# M501X.net
KiCad netlist of a schematic drawn in EAGLE
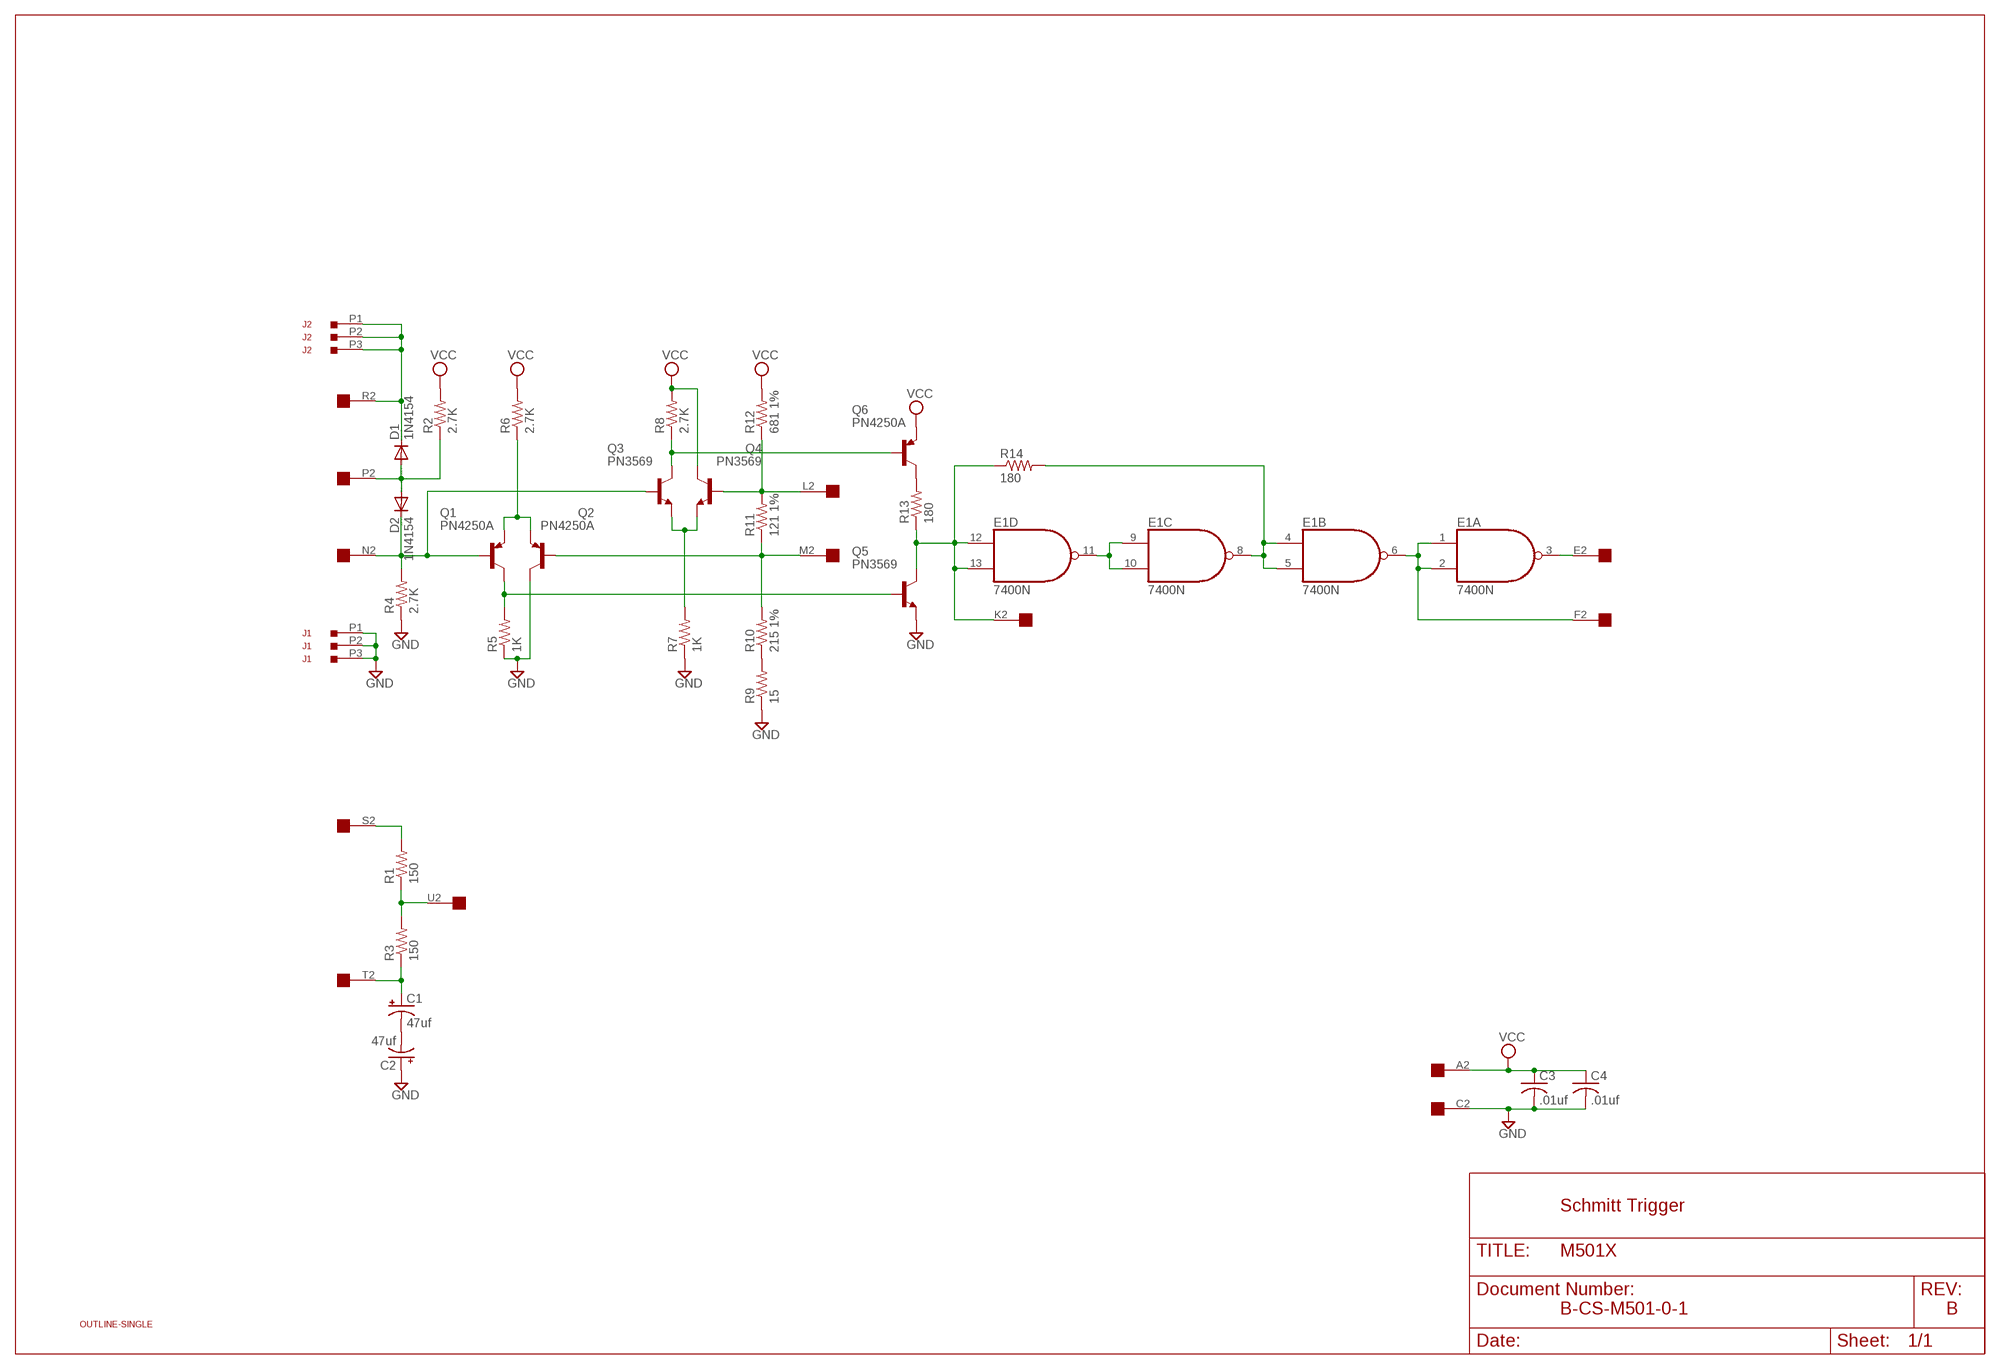
[diagram p0: schematic, sheet 1]

(export (version "E")
  (design (tool "Eeschema 10.0.6"))
  (components
    (comp (ref "C1")
      (value "47uf")
      (footprint "eagle-import:E22-6")
      (libsource (lib "eagle-import") (part "CPOL-USE22-6AXIAL"))
    )
    (comp (ref "C2")
      (value "47uf")
      (footprint "eagle-import:E22-6")
      (libsource (lib "eagle-import") (part "CPOL-USE22-6AXIAL"))
    )
    (comp (ref "C3")
      (value ".01uf")
      (footprint "eagle-import:C075-032X103")
      (libsource (lib "eagle-import") (part "C-US075-032X103"))
    )
    (comp (ref "C4")
      (value ".01uf")
      (footprint "eagle-import:C075-032X103")
      (libsource (lib "eagle-import") (part "C-US075-032X103"))
    )
    (comp (ref "D1")
      (value "1N4154")
      (footprint "eagle-import:DO35-10")
      (libsource (lib "eagle-import") (part "1N4148DO35-10"))
    )
    (comp (ref "D2")
      (value "1N4154")
      (footprint "eagle-import:DO35-10")
      (libsource (lib "eagle-import") (part "1N4148DO35-10"))
    )
    (comp (ref "E1")
      (value "7400N")
      (footprint "eagle-import:DIL14")
      (libsource (lib "eagle-import") (part "7400N"))
    )
    (comp (ref "J1")
      (value "34-22-1-03")
      (footprint "eagle-import:34-22-1-03")
      (libsource (lib "eagle-import") (part "34-22-1-03"))
    )
    (comp (ref "J2")
      (value "34-22-1-03")
      (footprint "eagle-import:34-22-1-03")
      (libsource (lib "eagle-import") (part "34-22-1-03"))
    )
    (comp (ref "Q1")
      (value "PN4250A")
      (footprint "eagle-import:TO39")
      (libsource (lib "eagle-import") (part "2N2904"))
    )
    (comp (ref "Q2")
      (value "PN4250A")
      (footprint "eagle-import:TO39")
      (libsource (lib "eagle-import") (part "2N2904"))
    )
    (comp (ref "Q3")
      (value "PN3569")
      (footprint "eagle-import:TO39")
      (libsource (lib "eagle-import") (part "2N3019"))
    )
    (comp (ref "Q4")
      (value "PN3569")
      (footprint "eagle-import:TO39")
      (libsource (lib "eagle-import") (part "2N3019"))
    )
    (comp (ref "Q5")
      (value "PN3569")
      (footprint "eagle-import:TO39")
      (libsource (lib "eagle-import") (part "2N3019"))
    )
    (comp (ref "Q6")
      (value "PN4250A")
      (footprint "eagle-import:TO39")
      (libsource (lib "eagle-import") (part "2N2904"))
    )
    (comp (ref "R1")
      (value "150")
      (footprint "eagle-import:0207_10")
      (libsource (lib "eagle-import") (part "R-US_0207/10"))
    )
    (comp (ref "R2")
      (value "2.7K")
      (footprint "eagle-import:0207_10")
      (libsource (lib "eagle-import") (part "R-US_0207/10"))
    )
    (comp (ref "R3")
      (value "150")
      (footprint "eagle-import:0207_10")
      (libsource (lib "eagle-import") (part "R-US_0207/10"))
    )
    (comp (ref "R4")
      (value "2.7K")
      (footprint "eagle-import:0207_10")
      (libsource (lib "eagle-import") (part "R-US_0207/10"))
    )
    (comp (ref "R5")
      (value "1K")
      (footprint "eagle-import:0207_10")
      (libsource (lib "eagle-import") (part "R-US_0207/10"))
    )
    (comp (ref "R6")
      (value "2.7K")
      (footprint "eagle-import:0207_10")
      (libsource (lib "eagle-import") (part "R-US_0207/10"))
    )
    (comp (ref "R7")
      (value "1K")
      (footprint "eagle-import:0207_10")
      (libsource (lib "eagle-import") (part "R-US_0207/10"))
    )
    (comp (ref "R8")
      (value "2.7K")
      (footprint "eagle-import:0207_10")
      (libsource (lib "eagle-import") (part "R-US_0207/10"))
    )
    (comp (ref "R9")
      (value "15")
      (footprint "eagle-import:0207_10")
      (libsource (lib "eagle-import") (part "R-US_0207/10"))
    )
    (comp (ref "R10")
      (value "215 1%")
      (footprint "eagle-import:0207_15")
      (libsource (lib "eagle-import") (part "R-US_0207/15"))
    )
    (comp (ref "R11")
      (value "121 1%")
      (footprint "eagle-import:0207_15")
      (libsource (lib "eagle-import") (part "R-US_0207/15"))
    )
    (comp (ref "R12")
      (value "681 1%")
      (footprint "eagle-import:0207_15")
      (libsource (lib "eagle-import") (part "R-US_0207/15"))
    )
    (comp (ref "R13")
      (value "180")
      (footprint "eagle-import:0207_10")
      (libsource (lib "eagle-import") (part "R-US_0207/10"))
    )
    (comp (ref "R14")
      (value "180")
      (footprint "eagle-import:0207_10")
      (libsource (lib "eagle-import") (part "R-US_0207/10"))
    )
    (comp (ref "U$1")
      (value "EDGE-1")
      (footprint "eagle-import:EDGE-CON1")
      (libsource (lib "eagle-import") (part "EDGE-1"))
    )
    (comp (ref "U$4")
      (value "OUTLINE-SINGLE")
      (footprint "eagle-import:SINGLE")
      (libsource (lib "eagle-import") (part "OUTLINE-SINGLE"))
    )
  )
  (nets
    (net (code "1") (name "GND") (class "Default")
      (node (ref "C2") (pin "+") (pinfunction "+_+") (pintype "passive"))
      (node (ref "C3") (pin "2") (pinfunction "2_2") (pintype "passive"))
      (node (ref "C4") (pin "2") (pinfunction "2_2") (pintype "passive"))
      (node (ref "J1") (pin "P1") (pinfunction "P$2_P1") (pintype "bidirectional"))
      (node (ref "J1") (pin "P2") (pinfunction "P$2_P2") (pintype "bidirectional"))
      (node (ref "J1") (pin "P3") (pinfunction "P$2_P3") (pintype "bidirectional"))
      (node (ref "Q2") (pin "3") (pinfunction "C_3") (pintype "passive"))
      (node (ref "Q5") (pin "1") (pinfunction "E_1") (pintype "passive"))
      (node (ref "R4") (pin "1") (pinfunction "1_1") (pintype "passive"))
      (node (ref "R5") (pin "1") (pinfunction "1_1") (pintype "passive"))
      (node (ref "R7") (pin "1") (pinfunction "1_1") (pintype "passive"))
      (node (ref "R9") (pin "1") (pinfunction "1_1") (pintype "passive"))
      (node (ref "U$1") (pin "C2") (pinfunction "1_C2") (pintype "bidirectional"))
    )
    (net (code "2") (name "Net-(C1-Pad-)") (class "Default")
      (node (ref "C1") (pin "-") (pinfunction "-_-") (pintype "passive"))
      (node (ref "C2") (pin "-") (pinfunction "-_-") (pintype "passive"))
    )
    (net (code "3") (name "Net-(E1A-I0)") (class "Default")
      (node (ref "E1") (pin "1") (pinfunction "I0_1") (pintype "input"))
      (node (ref "E1") (pin "2") (pinfunction "I1_2") (pintype "input"))
      (node (ref "E1") (pin "6") (pinfunction "O_6") (pintype "output"))
      (node (ref "U$1") (pin "F2") (pinfunction "1_F2") (pintype "bidirectional"))
    )
    (net (code "4") (name "Net-(E1A-O)") (class "Default")
      (node (ref "E1") (pin "3") (pinfunction "O_3") (pintype "output"))
      (node (ref "U$1") (pin "E2") (pinfunction "1_E2") (pintype "bidirectional"))
    )
    (net (code "5") (name "Net-(E1B-I0)") (class "Default")
      (node (ref "E1") (pin "4") (pinfunction "I0_4") (pintype "input"))
      (node (ref "E1") (pin "5") (pinfunction "I1_5") (pintype "input"))
      (node (ref "E1") (pin "8") (pinfunction "O_8") (pintype "output"))
      (node (ref "R14") (pin "2") (pinfunction "2_2") (pintype "passive"))
    )
    (net (code "6") (name "Net-(E1C-I0)") (class "Default")
      (node (ref "E1") (pin "10") (pinfunction "I1_10") (pintype "input"))
      (node (ref "E1") (pin "11") (pinfunction "O_11") (pintype "output"))
      (node (ref "E1") (pin "9") (pinfunction "I0_9") (pintype "input"))
    )
    (net (code "7") (name "Net-(E1D-I0)") (class "Default")
      (node (ref "E1") (pin "12") (pinfunction "I0_12") (pintype "input"))
      (node (ref "E1") (pin "13") (pinfunction "I1_13") (pintype "input"))
      (node (ref "Q5") (pin "3") (pinfunction "C_3") (pintype "passive"))
      (node (ref "R13") (pin "1") (pinfunction "1_1") (pintype "passive"))
      (node (ref "R14") (pin "1") (pinfunction "1_1") (pintype "passive"))
      (node (ref "U$1") (pin "K2") (pinfunction "1_K2") (pintype "bidirectional"))
    )
    (net (code "8") (name "Net-(J2A-P$2)") (class "Default")
      (node (ref "D1") (pin "C") (pinfunction "C_C") (pintype "passive"))
      (node (ref "J2") (pin "P1") (pinfunction "P$2_P1") (pintype "bidirectional"))
      (node (ref "J2") (pin "P2") (pinfunction "P$2_P2") (pintype "bidirectional"))
      (node (ref "J2") (pin "P3") (pinfunction "P$2_P3") (pintype "bidirectional"))
      (node (ref "U$1") (pin "R2") (pinfunction "1_R2") (pintype "bidirectional"))
    )
    (net (code "9") (name "Net-(Q1-B)") (class "Default")
      (node (ref "D2") (pin "C") (pinfunction "C_C") (pintype "passive"))
      (node (ref "Q1") (pin "2") (pinfunction "B_2") (pintype "passive"))
      (node (ref "Q3") (pin "2") (pinfunction "B_2") (pintype "passive"))
      (node (ref "R4") (pin "2") (pinfunction "2_2") (pintype "passive"))
      (node (ref "U$1") (pin "N2") (pinfunction "1_N2") (pintype "bidirectional"))
    )
    (net (code "10") (name "Net-(Q1-C)") (class "Default")
      (node (ref "Q1") (pin "3") (pinfunction "C_3") (pintype "passive"))
      (node (ref "Q5") (pin "2") (pinfunction "B_2") (pintype "passive"))
      (node (ref "R5") (pin "2") (pinfunction "2_2") (pintype "passive"))
    )
    (net (code "11") (name "Net-(Q1-E)") (class "Default")
      (node (ref "Q1") (pin "1") (pinfunction "E_1") (pintype "passive"))
      (node (ref "Q2") (pin "1") (pinfunction "E_1") (pintype "passive"))
      (node (ref "R6") (pin "1") (pinfunction "1_1") (pintype "passive"))
    )
    (net (code "12") (name "Net-(Q2-B)") (class "Default")
      (node (ref "Q2") (pin "2") (pinfunction "B_2") (pintype "passive"))
      (node (ref "R10") (pin "2") (pinfunction "2_2") (pintype "passive"))
      (node (ref "R11") (pin "1") (pinfunction "1_1") (pintype "passive"))
      (node (ref "U$1") (pin "M2") (pinfunction "1_M2") (pintype "bidirectional"))
    )
    (net (code "13") (name "Net-(Q3-C)") (class "Default")
      (node (ref "Q3") (pin "3") (pinfunction "C_3") (pintype "passive"))
      (node (ref "Q6") (pin "2") (pinfunction "B_2") (pintype "passive"))
      (node (ref "R8") (pin "1") (pinfunction "1_1") (pintype "passive"))
    )
    (net (code "14") (name "Net-(Q3-E)") (class "Default")
      (node (ref "Q3") (pin "1") (pinfunction "E_1") (pintype "passive"))
      (node (ref "Q4") (pin "1") (pinfunction "E_1") (pintype "passive"))
      (node (ref "R7") (pin "2") (pinfunction "2_2") (pintype "passive"))
    )
    (net (code "15") (name "Net-(Q4-B)") (class "Default")
      (node (ref "Q4") (pin "2") (pinfunction "B_2") (pintype "passive"))
      (node (ref "R11") (pin "2") (pinfunction "2_2") (pintype "passive"))
      (node (ref "R12") (pin "1") (pinfunction "1_1") (pintype "passive"))
      (node (ref "U$1") (pin "L2") (pinfunction "1_L2") (pintype "bidirectional"))
    )
    (net (code "16") (name "Net-(Q6-C)") (class "Default")
      (node (ref "Q6") (pin "3") (pinfunction "C_3") (pintype "passive"))
      (node (ref "R13") (pin "2") (pinfunction "2_2") (pintype "passive"))
    )
    (net (code "17") (name "Net-(R10-Pad1)") (class "Default")
      (node (ref "R10") (pin "1") (pinfunction "1_1") (pintype "passive"))
      (node (ref "R9") (pin "2") (pinfunction "2_2") (pintype "passive"))
    )
    (net (code "18") (name "Net-(U$1M-1)") (class "Default")
      (node (ref "D1") (pin "A") (pinfunction "A_A") (pintype "passive"))
      (node (ref "D2") (pin "A") (pinfunction "A_A") (pintype "passive"))
      (node (ref "R2") (pin "1") (pinfunction "1_1") (pintype "passive"))
      (node (ref "U$1") (pin "P2") (pinfunction "1_P2") (pintype "bidirectional"))
    )
    (net (code "19") (name "Net-(U$1O-1)") (class "Default")
      (node (ref "R1") (pin "2") (pinfunction "2_2") (pintype "passive"))
      (node (ref "U$1") (pin "S2") (pinfunction "1_S2") (pintype "bidirectional"))
    )
    (net (code "20") (name "Net-(U$1P-1)") (class "Default")
      (node (ref "C1") (pin "+") (pinfunction "+_+") (pintype "passive"))
      (node (ref "R3") (pin "1") (pinfunction "1_1") (pintype "passive"))
      (node (ref "U$1") (pin "T2") (pinfunction "1_T2") (pintype "bidirectional"))
    )
    (net (code "21") (name "Net-(U$1Q-1)") (class "Default")
      (node (ref "R1") (pin "1") (pinfunction "1_1") (pintype "passive"))
      (node (ref "R3") (pin "2") (pinfunction "2_2") (pintype "passive"))
      (node (ref "U$1") (pin "U2") (pinfunction "1_U2") (pintype "bidirectional"))
    )
    (net (code "22") (name "VCC") (class "Default")
      (node (ref "C3") (pin "1") (pinfunction "1_1") (pintype "passive"))
      (node (ref "C4") (pin "1") (pinfunction "1_1") (pintype "passive"))
      (node (ref "Q4") (pin "3") (pinfunction "C_3") (pintype "passive"))
      (node (ref "Q6") (pin "1") (pinfunction "E_1") (pintype "passive"))
      (node (ref "R12") (pin "2") (pinfunction "2_2") (pintype "passive"))
      (node (ref "R2") (pin "2") (pinfunction "2_2") (pintype "passive"))
      (node (ref "R6") (pin "2") (pinfunction "2_2") (pintype "passive"))
      (node (ref "R8") (pin "2") (pinfunction "2_2") (pintype "passive"))
      (node (ref "U$1") (pin "A2") (pinfunction "1_A2") (pintype "bidirectional"))
    )
  )
)
